# WMF_Ambient_SmartPot_C.net
KiCad netlist of a schematic drawn in EAGLE
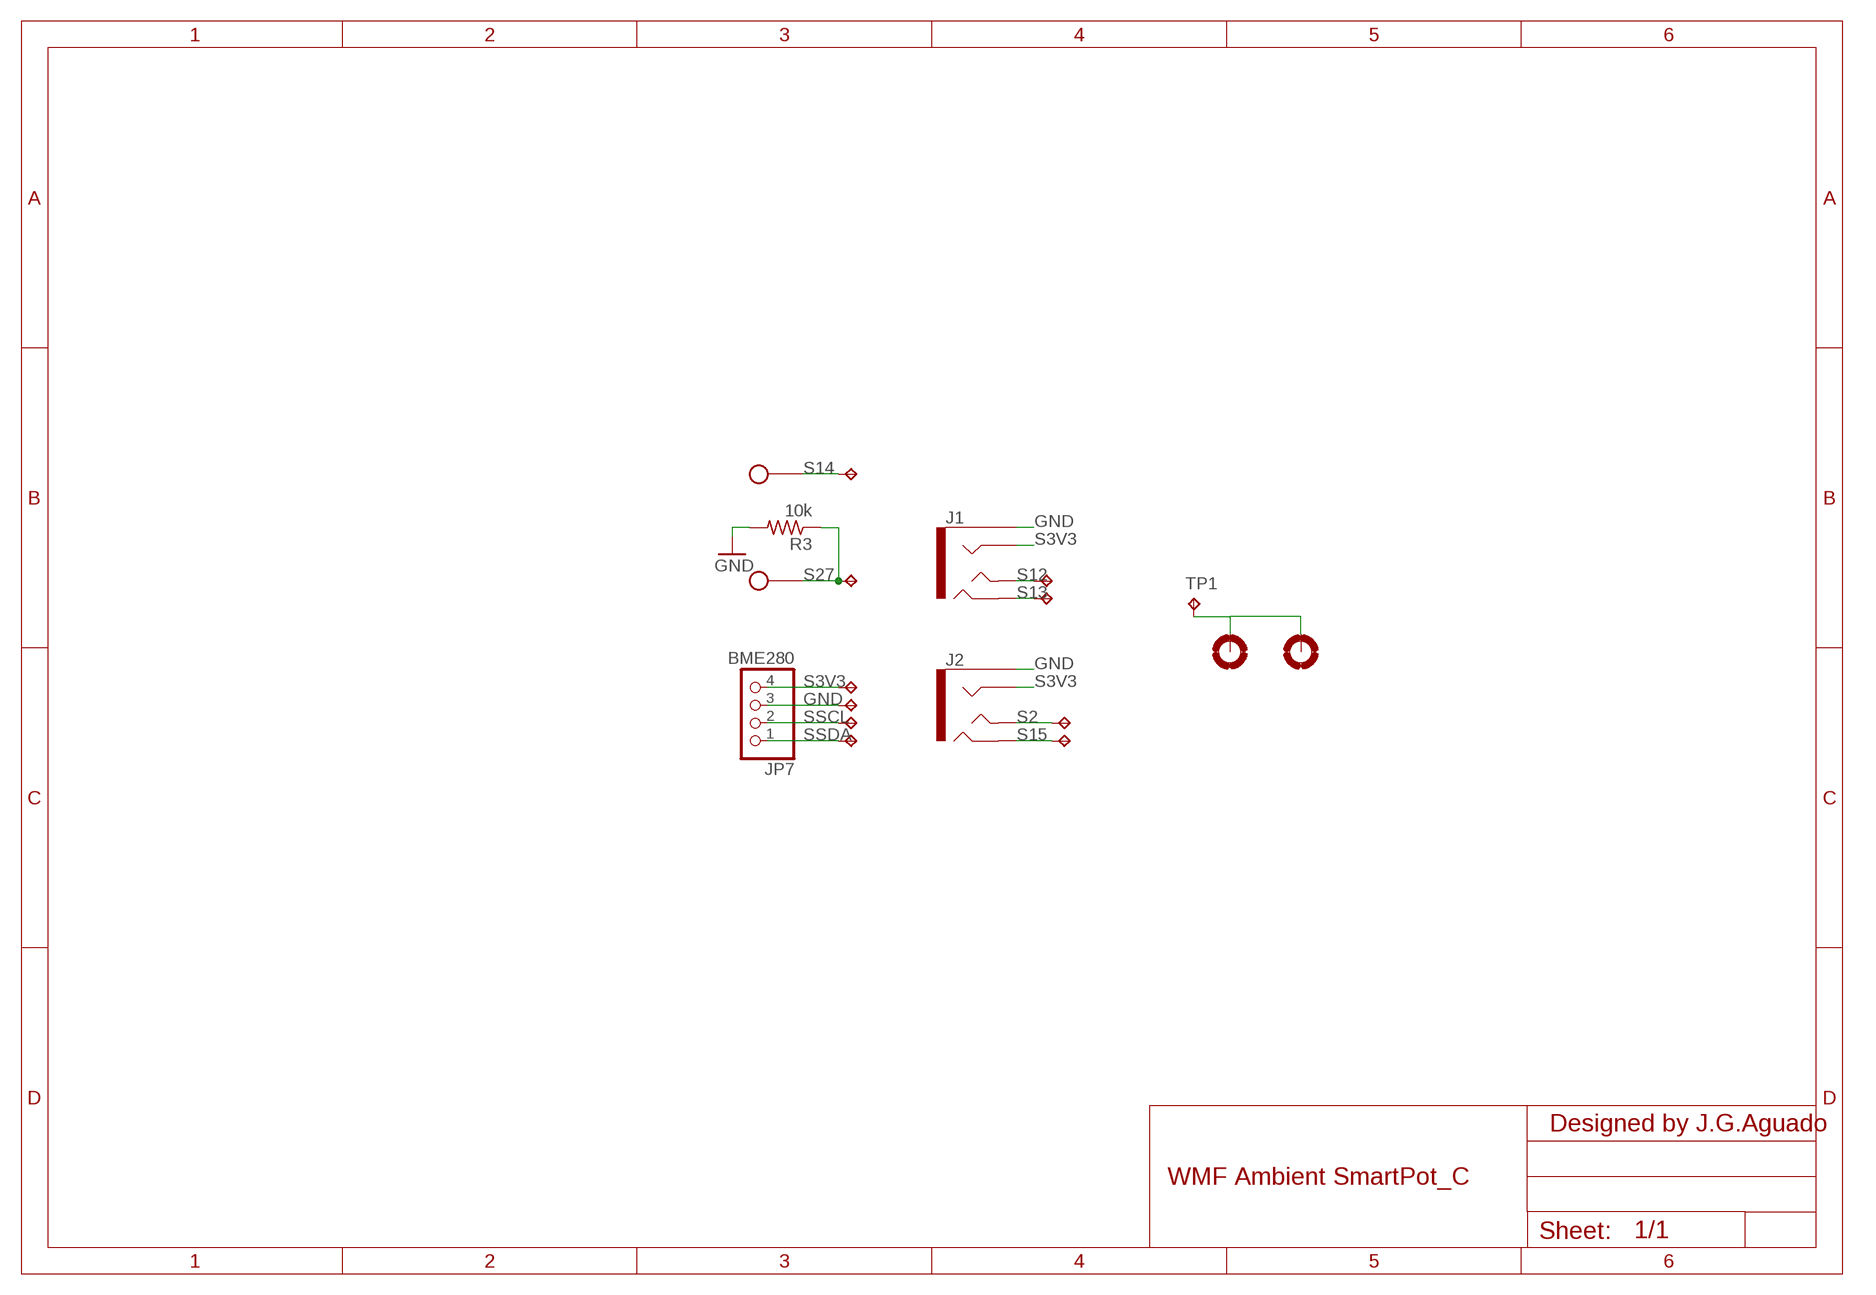
[diagram p0: schematic, sheet 1]

(export (version "E")
  (design (tool "Eeschema 10.0.6"))
  (components
    (comp (ref "H1")
      (value "MOUNT-PAD-ROUND2.8")
      (footprint "eagle-import:2,8-PAD")
      (libsource (lib "eagle-import") (part "MOUNT-PAD-ROUND2.8"))
    )
    (comp (ref "H2")
      (value "MOUNT-PAD-ROUND2.8")
      (footprint "eagle-import:2,8-PAD")
      (libsource (lib "eagle-import") (part "MOUNT-PAD-ROUND2.8"))
    )
    (comp (ref "J1")
      (value "AUDIO_JACK_TRRSSMD_RA")
      (footprint "eagle-import:AUDIO_JACK_3.5MM_TRRS_SMD_RA")
      (libsource (lib "eagle-import") (part "AUDIO_JACK_TRRSSMD_RA"))
    )
    (comp (ref "J2")
      (value "AUDIO_JACK_TRRSSMD_RA")
      (footprint "eagle-import:AUDIO_JACK_3.5MM_TRRS_SMD_RA")
      (libsource (lib "eagle-import") (part "AUDIO_JACK_TRRSSMD_RA"))
    )
    (comp (ref "JP7")
      (value "BME280")
      (footprint "eagle-import:1X04")
      (libsource (lib "eagle-import") (part "PINHD-1X4"))
    )
    (comp (ref "R3")
      (value "10k")
      (footprint "eagle-import:1206")
      (libsource (lib "eagle-import") (part "R1206"))
    )
    (comp (ref "TP1")
      (value "TPTP15SQ")
      (footprint "eagle-import:TP15SQ")
      (libsource (lib "eagle-import") (part "TPTP15SQ"))
    )
    (comp (ref "TP6")
      (value "TPTP15SQ")
      (footprint "eagle-import:TP15SQ")
      (libsource (lib "eagle-import") (part "TPTP15SQ"))
    )
    (comp (ref "TP7")
      (value "TPTP15SQ")
      (footprint "eagle-import:TP15SQ")
      (libsource (lib "eagle-import") (part "TPTP15SQ"))
    )
    (comp (ref "TP8")
      (value "TPTP15SQ")
      (footprint "eagle-import:TP15SQ")
      (libsource (lib "eagle-import") (part "TPTP15SQ"))
    )
    (comp (ref "TP9")
      (value "TPTP15SQ")
      (footprint "eagle-import:TP15SQ")
      (libsource (lib "eagle-import") (part "TPTP15SQ"))
    )
    (comp (ref "TP12")
      (value "TPTP15SQ")
      (footprint "eagle-import:TP15SQ")
      (libsource (lib "eagle-import") (part "TPTP15SQ"))
    )
    (comp (ref "TP16")
      (value "TPTP15SQ")
      (footprint "eagle-import:TP15SQ")
      (libsource (lib "eagle-import") (part "TPTP15SQ"))
    )
    (comp (ref "TP17")
      (value "TPTP15SQ")
      (footprint "eagle-import:TP15SQ")
      (libsource (lib "eagle-import") (part "TPTP15SQ"))
    )
    (comp (ref "TP20")
      (value "TPTP15SQ")
      (footprint "eagle-import:TP15SQ")
      (libsource (lib "eagle-import") (part "TPTP15SQ"))
    )
    (comp (ref "TP21")
      (value "TPTP15SQ")
      (footprint "eagle-import:TP15SQ")
      (libsource (lib "eagle-import") (part "TPTP15SQ"))
    )
    (comp (ref "TP23")
      (value "TPTP15SQ")
      (footprint "eagle-import:TP15SQ")
      (libsource (lib "eagle-import") (part "TPTP15SQ"))
    )
    (comp (ref "U$2")
      (value "OVAL_3MM_HOLE")
      (footprint "eagle-import:OVAL_HOLE")
      (libsource (lib "eagle-import") (part "OVAL_3MM_HOLE"))
    )
    (comp (ref "U$3")
      (value "OVAL_3MM_HOLE")
      (footprint "eagle-import:OVAL_HOLE")
      (libsource (lib "eagle-import") (part "OVAL_3MM_HOLE"))
    )
  )
  (nets
    (net (code "1") (name "/S2") (class "Default")
      (node (ref "J2") (pin "TIP") (pinfunction "TIP_TIP") (pintype "bidirectional"))
      (node (ref "TP20") (pin "TP") (pinfunction "TP_TP") (pintype "input"))
    )
    (net (code "2") (name "/S3V3") (class "Default")
      (node (ref "J1") (pin "RING1") (pinfunction "RING1_RING1") (pintype "bidirectional"))
      (node (ref "J2") (pin "RING1") (pinfunction "RING1_RING1") (pintype "bidirectional"))
      (node (ref "JP7") (pin "4") (pinfunction "4_4") (pintype "passive"))
      (node (ref "TP6") (pin "TP") (pinfunction "TP_TP") (pintype "input"))
    )
    (net (code "3") (name "/S12") (class "Default")
      (node (ref "J1") (pin "TIP") (pinfunction "TIP_TIP") (pintype "bidirectional"))
      (node (ref "TP16") (pin "TP") (pinfunction "TP_TP") (pintype "input"))
    )
    (net (code "4") (name "/S13") (class "Default")
      (node (ref "J1") (pin "RING2") (pinfunction "RING2_RING2") (pintype "bidirectional"))
      (node (ref "TP17") (pin "TP") (pinfunction "TP_TP") (pintype "input"))
    )
    (net (code "5") (name "/S14") (class "Default")
      (node (ref "TP12") (pin "TP") (pinfunction "TP_TP") (pintype "input"))
      (node (ref "U$2") (pin "P$2") (pinfunction "P$1_P$2") (pintype "bidirectional"))
    )
    (net (code "6") (name "/S15") (class "Default")
      (node (ref "J2") (pin "RING2") (pinfunction "RING2_RING2") (pintype "bidirectional"))
      (node (ref "TP21") (pin "TP") (pinfunction "TP_TP") (pintype "input"))
    )
    (net (code "7") (name "/S27") (class "Default")
      (node (ref "R3") (pin "1") (pinfunction "1_1") (pintype "passive"))
      (node (ref "TP23") (pin "TP") (pinfunction "TP_TP") (pintype "input"))
      (node (ref "U$3") (pin "P$2") (pinfunction "P$1_P$2") (pintype "bidirectional"))
    )
    (net (code "8") (name "/SSCL") (class "Default")
      (node (ref "JP7") (pin "2") (pinfunction "2_2") (pintype "passive"))
      (node (ref "TP8") (pin "TP") (pinfunction "TP_TP") (pintype "input"))
    )
    (net (code "9") (name "/SSDA") (class "Default")
      (node (ref "JP7") (pin "1") (pinfunction "1_1") (pintype "passive"))
      (node (ref "TP9") (pin "TP") (pinfunction "TP_TP") (pintype "input"))
    )
    (net (code "10") (name "GND") (class "Default")
      (node (ref "J1") (pin "EARTH") (pinfunction "EARTH_EARTH") (pintype "bidirectional"))
      (node (ref "J2") (pin "EARTH") (pinfunction "EARTH_EARTH") (pintype "bidirectional"))
      (node (ref "JP7") (pin "3") (pinfunction "3_3") (pintype "passive"))
      (node (ref "R3") (pin "2") (pinfunction "2_2") (pintype "passive"))
      (node (ref "TP7") (pin "TP") (pinfunction "TP_TP") (pintype "input"))
    )
    (net (code "11") (name "Net-(H1-MOUNT)") (class "Default")
      (node (ref "H1") (pin "B2,8") (pinfunction "MOUNT_B2,8") (pintype "passive"))
      (node (ref "H2") (pin "B2,8") (pinfunction "MOUNT_B2,8") (pintype "passive"))
      (node (ref "TP1") (pin "TP") (pinfunction "TP_TP") (pintype "input"))
    )
  )
)
